# SD.net
KiCad netlist of a schematic drawn in Altium Designer
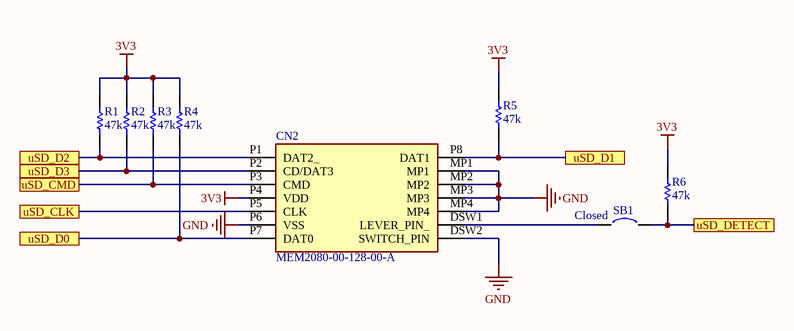
[diagram p0: SD.SchDoc]

(export (version "E")
  (design (tool "Eeschema 10.0.6"))
  (components
    (comp (ref "CN2")
      (value "MEM2080-00-128-00-A")
      (footprint "SamacSys:MEM20800012800A")
      (description "Connector")
      (fields (field (name "MOUSER PART NUMBER") "640-MEM2080-0012800A"))
      (libsource (lib "*") (part "MEM2080-00-128-00-A"))
    )
    (comp (ref "R1")
      (value "47k")
      (footprint "1608[0603]")
      (description "Resistor")
      (fields (field (name "Comment") "Res1") (field (name "PUBLISHER") "Altium Limited"))
      (libsource (lib "Miscellaneous Devices") (part "Res1"))
    )
    (comp (ref "R2")
      (value "47k")
      (footprint "1608[0603]")
      (description "Resistor")
      (fields (field (name "Comment") "Res1") (field (name "PUBLISHER") "Altium Limited"))
      (libsource (lib "Miscellaneous Devices") (part "Res1"))
    )
    (comp (ref "R3")
      (value "47k")
      (footprint "1608[0603]")
      (description "Resistor")
      (fields (field (name "Comment") "Res1") (field (name "PUBLISHER") "Altium Limited"))
      (libsource (lib "Miscellaneous Devices") (part "Res1"))
    )
    (comp (ref "R4")
      (value "47k")
      (footprint "1608[0603]")
      (description "Resistor")
      (fields (field (name "Comment") "Res1") (field (name "PUBLISHER") "Altium Limited"))
      (libsource (lib "Miscellaneous Devices") (part "Res1"))
    )
    (comp (ref "R5")
      (value "47k")
      (footprint "1608[0603]")
      (description "Resistor")
      (fields (field (name "Comment") "Res1") (field (name "PUBLISHER") "Altium Limited"))
      (libsource (lib "Miscellaneous Devices") (part "Res1"))
    )
    (comp (ref "R6")
      (value "47k")
      (footprint "1608[0603]")
      (description "Resistor")
      (fields (field (name "Comment") "Res1") (field (name "PUBLISHER") "Altium Limited"))
      (libsource (lib "Miscellaneous Devices") (part "Res1"))
    )
    (comp (ref "SB1")
      (value "Closed")
      (footprint "SB_0603")
      (description "Circuit Breaker")
      (fields (field (name "PUBLISHER") "Altium Limited"))
      (libsource (lib "MB1137") (part "Circuit Breaker"))
    )
  )
  (nets
    (net (code "1") (name "/uSD_CLK") (class "Default")
      (node (ref "CN2") (pin "P5") (pinfunction "CLK_P5") (pintype "passive"))
    )
    (net (code "2") (name "/uSD_CMD") (class "Default")
      (node (ref "CN2") (pin "P3") (pinfunction "CMD_P3") (pintype "passive"))
      (node (ref "R3") (pin "2") (pinfunction "2_2") (pintype "passive"))
    )
    (net (code "3") (name "/uSD_D0") (class "Default")
      (node (ref "CN2") (pin "P7") (pinfunction "DAT0_P7") (pintype "passive"))
      (node (ref "R4") (pin "2") (pinfunction "2_2") (pintype "passive"))
    )
    (net (code "4") (name "/uSD_D1") (class "Default")
      (node (ref "CN2") (pin "P8") (pinfunction "DAT1_P8") (pintype "passive"))
      (node (ref "R5") (pin "2") (pinfunction "2_2") (pintype "passive"))
    )
    (net (code "5") (name "/uSD_D2") (class "Default")
      (node (ref "CN2") (pin "P1") (pinfunction "DAT2__P1") (pintype "passive"))
      (node (ref "R1") (pin "2") (pinfunction "2_2") (pintype "passive"))
    )
    (net (code "6") (name "/uSD_D3") (class "Default")
      (node (ref "CN2") (pin "P2") (pinfunction "CD/DAT3_P2") (pintype "passive"))
      (node (ref "R2") (pin "2") (pinfunction "2_2") (pintype "passive"))
    )
    (net (code "7") (name "/uSD_DETECT") (class "Default")
      (node (ref "R6") (pin "1") (pinfunction "1_1") (pintype "passive"))
      (node (ref "SB1") (pin "2") (pinfunction "2_2") (pintype "passive"))
    )
    (net (code "8") (name "3V3") (class "Default")
      (node (ref "CN2") (pin "P4") (pinfunction "VDD_P4") (pintype "passive"))
      (node (ref "R1") (pin "1") (pinfunction "1_1") (pintype "passive"))
      (node (ref "R2") (pin "1") (pinfunction "1_1") (pintype "passive"))
      (node (ref "R3") (pin "1") (pinfunction "1_1") (pintype "passive"))
      (node (ref "R4") (pin "1") (pinfunction "1_1") (pintype "passive"))
      (node (ref "R5") (pin "1") (pinfunction "1_1") (pintype "passive"))
      (node (ref "R6") (pin "2") (pinfunction "2_2") (pintype "passive"))
    )
    (net (code "9") (name "GND") (class "Default")
      (node (ref "CN2") (pin "DSW2") (pinfunction "SWITCH_PIN_DSW2") (pintype "passive"))
      (node (ref "CN2") (pin "MP1") (pinfunction "MP1_MP1") (pintype "passive"))
      (node (ref "CN2") (pin "MP2") (pinfunction "MP2_MP2") (pintype "passive"))
      (node (ref "CN2") (pin "MP3") (pinfunction "MP3_MP3") (pintype "passive"))
      (node (ref "CN2") (pin "MP4") (pinfunction "MP4_MP4") (pintype "passive"))
      (node (ref "CN2") (pin "P6") (pinfunction "VSS_P6") (pintype "passive"))
    )
    (net (code "10") (name "Net-(CN2-LEVER_PIN_)") (class "Default")
      (node (ref "CN2") (pin "DSW1") (pinfunction "LEVER_PIN__DSW1") (pintype "passive"))
      (node (ref "SB1") (pin "1") (pinfunction "1_1") (pintype "passive"))
    )
  )
)
